# NE556-CD4069-Synth-Toy-2.net
KiCad netlist of a schematic drawn in EAGLE
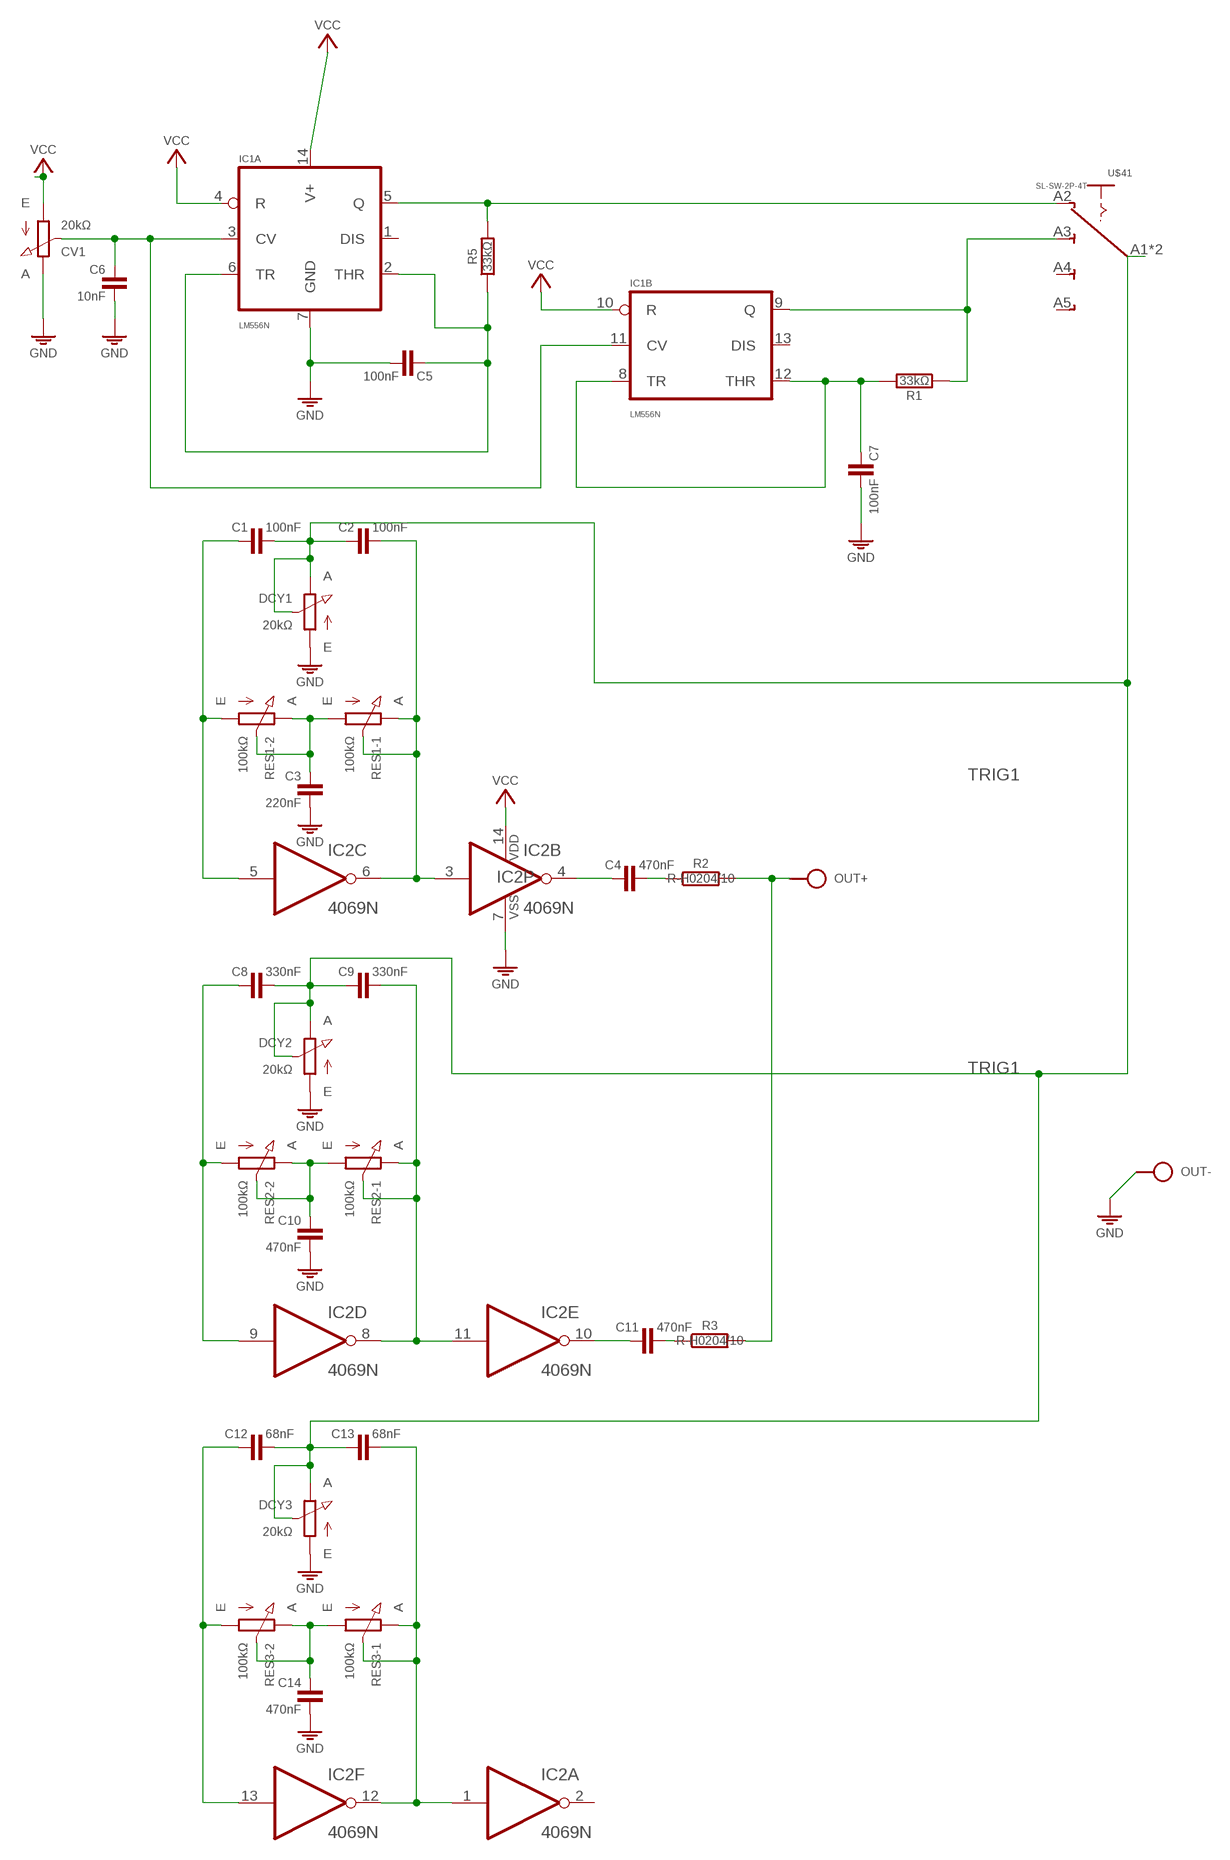
[diagram p0: schematic, sheet 1]

(export (version "E")
  (design (tool "Eeschema 10.0.6"))
  (components
    (comp (ref "C1")
      (value "100nF")
      (footprint "eagle-import:C050-024X044")
      (libsource (lib "eagle-import") (part "C-H050-024X044"))
    )
    (comp (ref "C2")
      (value "100nF")
      (footprint "eagle-import:C050-024X044")
      (libsource (lib "eagle-import") (part "C-H050-024X044"))
    )
    (comp (ref "C3")
      (value "220nF")
      (footprint "eagle-import:C050-020X044_V")
      (libsource (lib "eagle-import") (part "C050-020X044/V"))
    )
    (comp (ref "C4")
      (value "470nF")
      (footprint "eagle-import:C050-024X044")
      (libsource (lib "eagle-import") (part "C-H050-024X044"))
    )
    (comp (ref "C5")
      (value "100nF")
      (footprint "eagle-import:C050-020X044")
      (libsource (lib "eagle-import") (part "C-H050-020X044"))
    )
    (comp (ref "C6")
      (value "10nF")
      (footprint "eagle-import:C050-020X044_V")
      (libsource (lib "eagle-import") (part "C050-020X044/V"))
    )
    (comp (ref "C7")
      (value "100nF")
      (footprint "eagle-import:C050-020X044")
      (libsource (lib "eagle-import") (part "C-H050-020X044"))
    )
    (comp (ref "C8")
      (value "330nF")
      (footprint "eagle-import:C050-024X044")
      (libsource (lib "eagle-import") (part "C-H050-024X044"))
    )
    (comp (ref "C9")
      (value "330nF")
      (footprint "eagle-import:C050-024X044")
      (libsource (lib "eagle-import") (part "C-H050-024X044"))
    )
    (comp (ref "C10")
      (value "470nF")
      (footprint "eagle-import:C050-020X044_V")
      (libsource (lib "eagle-import") (part "C050-020X044/V"))
    )
    (comp (ref "C11")
      (value "470nF")
      (footprint "eagle-import:C050-024X044")
      (libsource (lib "eagle-import") (part "C-H050-024X044"))
    )
    (comp (ref "C12")
      (value "68nF")
      (footprint "eagle-import:C050-024X044")
      (libsource (lib "eagle-import") (part "C-H050-024X044"))
    )
    (comp (ref "C13")
      (value "68nF")
      (footprint "eagle-import:C050-024X044")
      (libsource (lib "eagle-import") (part "C-H050-024X044"))
    )
    (comp (ref "C14")
      (value "470nF")
      (footprint "eagle-import:C050-020X044_V")
      (libsource (lib "eagle-import") (part "C050-020X044/V"))
    )
    (comp (ref "CV1")
      (value "20kΩ")
      (footprint "eagle-import:POT")
      (libsource (lib "eagle-import") (part "POT"))
    )
    (comp (ref "DCY1")
      (value "20kΩ")
      (footprint "eagle-import:POT")
      (libsource (lib "eagle-import") (part "POT"))
    )
    (comp (ref "DCY2")
      (value "20kΩ")
      (footprint "eagle-import:POT")
      (libsource (lib "eagle-import") (part "POT"))
    )
    (comp (ref "DCY3")
      (value "20kΩ")
      (footprint "eagle-import:POT")
      (libsource (lib "eagle-import") (part "POT"))
    )
    (comp (ref "IC1")
      (value "LM556N")
      (footprint "eagle-import:DIL14")
      (libsource (lib "eagle-import") (part "556NLM"))
    )
    (comp (ref "IC2")
      (value "4069N")
      (footprint "eagle-import:DIL14")
      (libsource (lib "eagle-import") (part "4069N"))
    )
    (comp (ref "OUT")
      (value "SPAD+-+-")
      (footprint "eagle-import:SPAD+-")
      (libsource (lib "eagle-import") (part "SPAD+-+-"))
    )
    (comp (ref "R1")
      (value "33kΩ")
      (footprint "eagle-import:0204_10-V")
      (libsource (lib "eagle-import") (part "R-H0204/10-V"))
    )
    (comp (ref "R2")
      (value "R-H0204/10")
      (footprint "eagle-import:0204_10")
      (libsource (lib "eagle-import") (part "R-H0204/10"))
    )
    (comp (ref "R3")
      (value "R-H0204/10")
      (footprint "eagle-import:0204_10")
      (libsource (lib "eagle-import") (part "R-H0204/10"))
    )
    (comp (ref "R5")
      (value "33kΩ")
      (footprint "eagle-import:0204_10-V")
      (libsource (lib "eagle-import") (part "R-H0204/10-V"))
    )
    (comp (ref "RES1")
      (value "100kΩ")
      (footprint "eagle-import:POT-STEREO-2X3")
      (libsource (lib "eagle-import") (part "POT-STEREO"))
    )
    (comp (ref "RES2")
      (value "100kΩ")
      (footprint "eagle-import:POT-STEREO-2X3")
      (libsource (lib "eagle-import") (part "POT-STEREO"))
    )
    (comp (ref "RES3")
      (value "100kΩ")
      (footprint "eagle-import:POT-STEREO-1X6-V")
      (libsource (lib "eagle-import") (part "POT-STEREO-1X6-V"))
    )
    (comp (ref "S3")
      (value "VCC_GNDPWR-L")
      (footprint "eagle-import:PWR-L")
      (libsource (lib "eagle-import") (part "VCC_GNDPWR-L"))
    )
    (comp (ref "U$4")
      (value "SL-SW-2P-4T")
      (footprint "eagle-import:SLSW-2P4T-2-H")
      (libsource (lib "eagle-import") (part "SL-SW-2P-4T"))
    )
  )
  (nets
    (net (code "1") (name "/TRIG1") (class "Default")
      (node (ref "C1") (pin "2") (pinfunction "2_2") (pintype "passive"))
      (node (ref "C12") (pin "2") (pinfunction "2_2") (pintype "passive"))
      (node (ref "C13") (pin "1") (pinfunction "1_1") (pintype "passive"))
      (node (ref "C2") (pin "1") (pinfunction "1_1") (pintype "passive"))
      (node (ref "C8") (pin "2") (pinfunction "2_2") (pintype "passive"))
      (node (ref "C9") (pin "1") (pinfunction "1_1") (pintype "passive"))
      (node (ref "DCY1") (pin "E") (pinfunction "E_E") (pintype "passive"))
      (node (ref "DCY1") (pin "S") (pinfunction "S_S") (pintype "passive"))
      (node (ref "DCY2") (pin "E") (pinfunction "E_E") (pintype "passive"))
      (node (ref "DCY2") (pin "S") (pinfunction "S_S") (pintype "passive"))
      (node (ref "DCY3") (pin "E") (pinfunction "E_E") (pintype "passive"))
      (node (ref "DCY3") (pin "S") (pinfunction "S_S") (pintype "passive"))
      (node (ref "U$4") (pin "A1") (pinfunction "P_A1") (pintype "passive"))
      (node (ref "U$4") (pin "A6") (pinfunction "P_A6") (pintype "passive"))
    )
    (net (code "2") (name "GND") (class "Default")
      (node (ref "C10") (pin "2") (pinfunction "2_2") (pintype "passive"))
      (node (ref "C14") (pin "2") (pinfunction "2_2") (pintype "passive"))
      (node (ref "C3") (pin "2") (pinfunction "2_2") (pintype "passive"))
      (node (ref "C5") (pin "2") (pinfunction "2_2") (pintype "passive"))
      (node (ref "C6") (pin "2") (pinfunction "2_2") (pintype "passive"))
      (node (ref "C7") (pin "2") (pinfunction "2_2") (pintype "passive"))
      (node (ref "CV1") (pin "E") (pinfunction "E_E") (pintype "passive"))
      (node (ref "DCY1") (pin "A") (pinfunction "A_A") (pintype "passive"))
      (node (ref "DCY2") (pin "A") (pinfunction "A_A") (pintype "passive"))
      (node (ref "DCY3") (pin "A") (pinfunction "A_A") (pintype "passive"))
      (node (ref "IC1") (pin "7") (pinfunction "GND_7") (pintype "power_in"))
      (node (ref "IC2") (pin "7") (pinfunction "VSS_7") (pintype "power_in"))
      (node (ref "OUT") (pin "1") (pinfunction "P$1_1") (pintype "passive"))
      (node (ref "S3") (pin "1") (pinfunction "GND_1") (pintype "power_in"))
    )
    (net (code "3") (name "Net-(C4-Pad2)") (class "Default")
      (node (ref "C4") (pin "2") (pinfunction "2_2") (pintype "passive"))
      (node (ref "R2") (pin "1") (pinfunction "1_1") (pintype "passive"))
    )
    (net (code "4") (name "Net-(C11-Pad2)") (class "Default")
      (node (ref "C11") (pin "2") (pinfunction "2_2") (pintype "passive"))
      (node (ref "R3") (pin "1") (pinfunction "1_1") (pintype "passive"))
    )
    (net (code "5") (name "Net-(IC1A-CV)") (class "Default")
      (node (ref "C6") (pin "1") (pinfunction "1_1") (pintype "passive"))
      (node (ref "CV1") (pin "S") (pinfunction "S_S") (pintype "passive"))
      (node (ref "IC1") (pin "11") (pinfunction "CV_11") (pintype "input"))
      (node (ref "IC1") (pin "3") (pinfunction "CV_3") (pintype "input"))
    )
    (net (code "6") (name "Net-(IC1A-Q)") (class "Default")
      (node (ref "IC1") (pin "5") (pinfunction "Q_5") (pintype "output"))
      (node (ref "R5") (pin "2") (pinfunction "2_2") (pintype "passive"))
      (node (ref "U$4") (pin "A2") (pinfunction "A_A2") (pintype "passive"))
    )
    (net (code "7") (name "Net-(IC1A-THR)") (class "Default")
      (node (ref "C5") (pin "1") (pinfunction "1_1") (pintype "passive"))
      (node (ref "IC1") (pin "2") (pinfunction "THR_2") (pintype "input"))
      (node (ref "IC1") (pin "6") (pinfunction "TR_6") (pintype "input"))
      (node (ref "R5") (pin "1") (pinfunction "1_1") (pintype "passive"))
    )
    (net (code "8") (name "Net-(IC1B-Q)") (class "Default")
      (node (ref "IC1") (pin "9") (pinfunction "Q_9") (pintype "output"))
      (node (ref "R1") (pin "1") (pinfunction "1_1") (pintype "passive"))
      (node (ref "U$4") (pin "A3") (pinfunction "B_A3") (pintype "passive"))
    )
    (net (code "9") (name "Net-(IC1B-THR)") (class "Default")
      (node (ref "C7") (pin "1") (pinfunction "1_1") (pintype "passive"))
      (node (ref "IC1") (pin "12") (pinfunction "THR_12") (pintype "input"))
      (node (ref "IC1") (pin "8") (pinfunction "TR_8") (pintype "input"))
      (node (ref "R1") (pin "2") (pinfunction "2_2") (pintype "passive"))
    )
    (net (code "10") (name "Net-(IC2A-I)") (class "Default")
      (node (ref "C13") (pin "2") (pinfunction "2_2") (pintype "passive"))
      (node (ref "IC2") (pin "1") (pinfunction "I_1") (pintype "input"))
      (node (ref "IC2") (pin "12") (pinfunction "O_12") (pintype "output"))
      (node (ref "RES3") (pin "1E") (pinfunction "E_1E") (pintype "passive"))
      (node (ref "RES3") (pin "1S") (pinfunction "S_1S") (pintype "passive"))
    )
    (net (code "11") (name "Net-(IC2B-I)") (class "Default")
      (node (ref "C2") (pin "2") (pinfunction "2_2") (pintype "passive"))
      (node (ref "IC2") (pin "3") (pinfunction "I_3") (pintype "input"))
      (node (ref "IC2") (pin "6") (pinfunction "O_6") (pintype "output"))
      (node (ref "RES1") (pin "1-E") (pinfunction "E_1-E") (pintype "passive"))
      (node (ref "RES1") (pin "1-S") (pinfunction "S_1-S") (pintype "passive"))
    )
    (net (code "12") (name "Net-(IC2B-O)") (class "Default")
      (node (ref "C4") (pin "1") (pinfunction "1_1") (pintype "passive"))
      (node (ref "IC2") (pin "4") (pinfunction "O_4") (pintype "output"))
    )
    (net (code "13") (name "Net-(IC2C-I)") (class "Default")
      (node (ref "C1") (pin "1") (pinfunction "1_1") (pintype "passive"))
      (node (ref "IC2") (pin "5") (pinfunction "I_5") (pintype "input"))
      (node (ref "RES1") (pin "2-A") (pinfunction "A_2-A") (pintype "passive"))
    )
    (net (code "14") (name "Net-(IC2D-I)") (class "Default")
      (node (ref "C8") (pin "1") (pinfunction "1_1") (pintype "passive"))
      (node (ref "IC2") (pin "9") (pinfunction "I_9") (pintype "input"))
      (node (ref "RES2") (pin "2-A") (pinfunction "A_2-A") (pintype "passive"))
    )
    (net (code "15") (name "Net-(IC2D-O)") (class "Default")
      (node (ref "C9") (pin "2") (pinfunction "2_2") (pintype "passive"))
      (node (ref "IC2") (pin "11") (pinfunction "I_11") (pintype "input"))
      (node (ref "IC2") (pin "8") (pinfunction "O_8") (pintype "output"))
      (node (ref "RES2") (pin "1-E") (pinfunction "E_1-E") (pintype "passive"))
      (node (ref "RES2") (pin "1-S") (pinfunction "S_1-S") (pintype "passive"))
    )
    (net (code "16") (name "Net-(IC2E-O)") (class "Default")
      (node (ref "C11") (pin "1") (pinfunction "1_1") (pintype "passive"))
      (node (ref "IC2") (pin "10") (pinfunction "O_10") (pintype "output"))
    )
    (net (code "17") (name "Net-(IC2F-I)") (class "Default")
      (node (ref "C12") (pin "1") (pinfunction "1_1") (pintype "passive"))
      (node (ref "IC2") (pin "13") (pinfunction "I_13") (pintype "input"))
      (node (ref "RES3") (pin "2A") (pinfunction "A_2A") (pintype "passive"))
    )
    (net (code "18") (name "Net-(OUTA-P$1)") (class "Default")
      (node (ref "OUT") (pin "2") (pinfunction "P$1_2") (pintype "passive"))
      (node (ref "R2") (pin "2") (pinfunction "2_2") (pintype "passive"))
      (node (ref "R3") (pin "2") (pinfunction "2_2") (pintype "passive"))
    )
    (net (code "19") (name "Net-(RES1A-A)") (class "Default")
      (node (ref "C3") (pin "1") (pinfunction "1_1") (pintype "passive"))
      (node (ref "RES1") (pin "1-A") (pinfunction "A_1-A") (pintype "passive"))
      (node (ref "RES1") (pin "2-E") (pinfunction "E_2-E") (pintype "passive"))
      (node (ref "RES1") (pin "2-S") (pinfunction "S_2-S") (pintype "passive"))
    )
    (net (code "20") (name "Net-(RES2A-A)") (class "Default")
      (node (ref "C10") (pin "1") (pinfunction "1_1") (pintype "passive"))
      (node (ref "RES2") (pin "1-A") (pinfunction "A_1-A") (pintype "passive"))
      (node (ref "RES2") (pin "2-E") (pinfunction "E_2-E") (pintype "passive"))
      (node (ref "RES2") (pin "2-S") (pinfunction "S_2-S") (pintype "passive"))
    )
    (net (code "21") (name "Net-(RES3A-A)") (class "Default")
      (node (ref "C14") (pin "1") (pinfunction "1_1") (pintype "passive"))
      (node (ref "RES3") (pin "1A") (pinfunction "A_1A") (pintype "passive"))
      (node (ref "RES3") (pin "2E") (pinfunction "E_2E") (pintype "passive"))
      (node (ref "RES3") (pin "2S") (pinfunction "S_2S") (pintype "passive"))
    )
    (net (code "22") (name "VCC") (class "Default")
      (node (ref "CV1") (pin "A") (pinfunction "A_A") (pintype "passive"))
      (node (ref "IC1") (pin "10") (pinfunction "R_10") (pintype "input"))
      (node (ref "IC1") (pin "14") (pinfunction "V+_14") (pintype "power_in"))
      (node (ref "IC1") (pin "4") (pinfunction "R_4") (pintype "input"))
      (node (ref "IC2") (pin "14") (pinfunction "VDD_14") (pintype "power_in"))
      (node (ref "S3") (pin "2") (pinfunction "VCC_2") (pintype "power_in"))
    )
    (net (code "23") (name "unconnected-(IC1A-DIS-Pad1)") (class "Default")
      (node (ref "IC1") (pin "1") (pinfunction "DIS_1") (pintype "passive"))
    )
    (net (code "24") (name "unconnected-(IC1B-DIS-Pad13)") (class "Default")
      (node (ref "IC1") (pin "13") (pinfunction "DIS_13") (pintype "input"))
    )
    (net (code "25") (name "unconnected-(IC2A-O-Pad2)") (class "Default")
      (node (ref "IC2") (pin "2") (pinfunction "O_2") (pintype "output"))
    )
    (net (code "26") (name "unconnected-(U$4A-C-PadA4)") (class "Default")
      (node (ref "U$4") (pin "A4") (pinfunction "C_A4") (pintype "passive"))
    )
    (net (code "27") (name "unconnected-(U$4A-D-PadA5)") (class "Default")
      (node (ref "U$4") (pin "A5") (pinfunction "D_A5") (pintype "passive"))
    )
  )
)
